# hs-256-expansion-debug.net
KiCad netlist of a schematic drawn in EAGLE
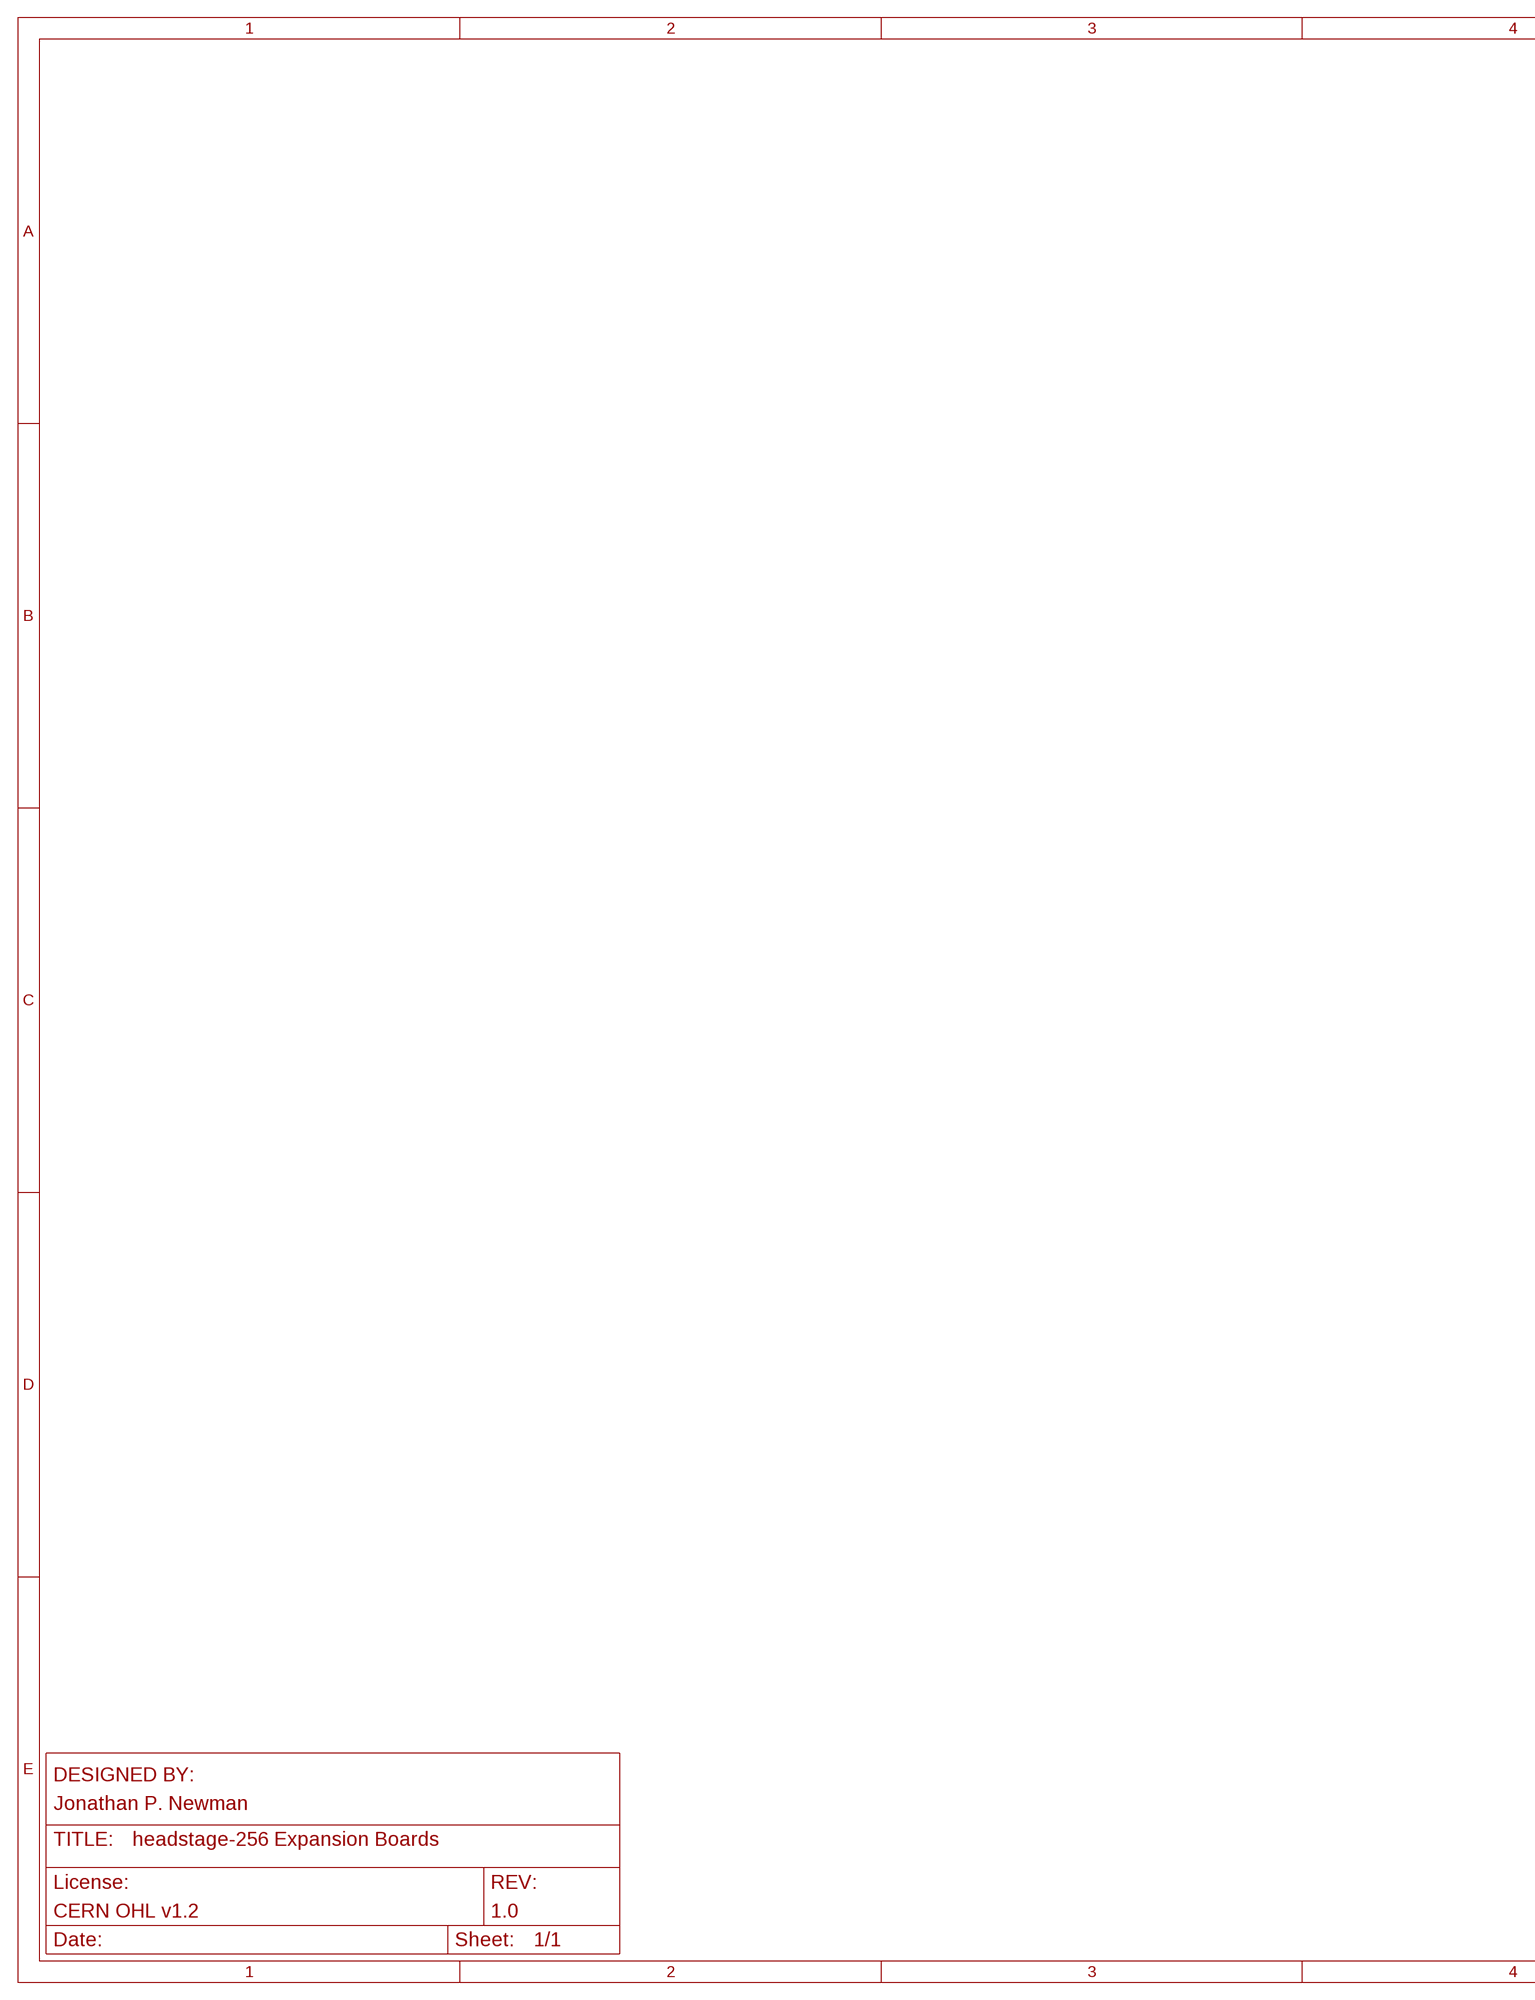
[diagram p0: schematic, sheet 1, part 1 of 2]
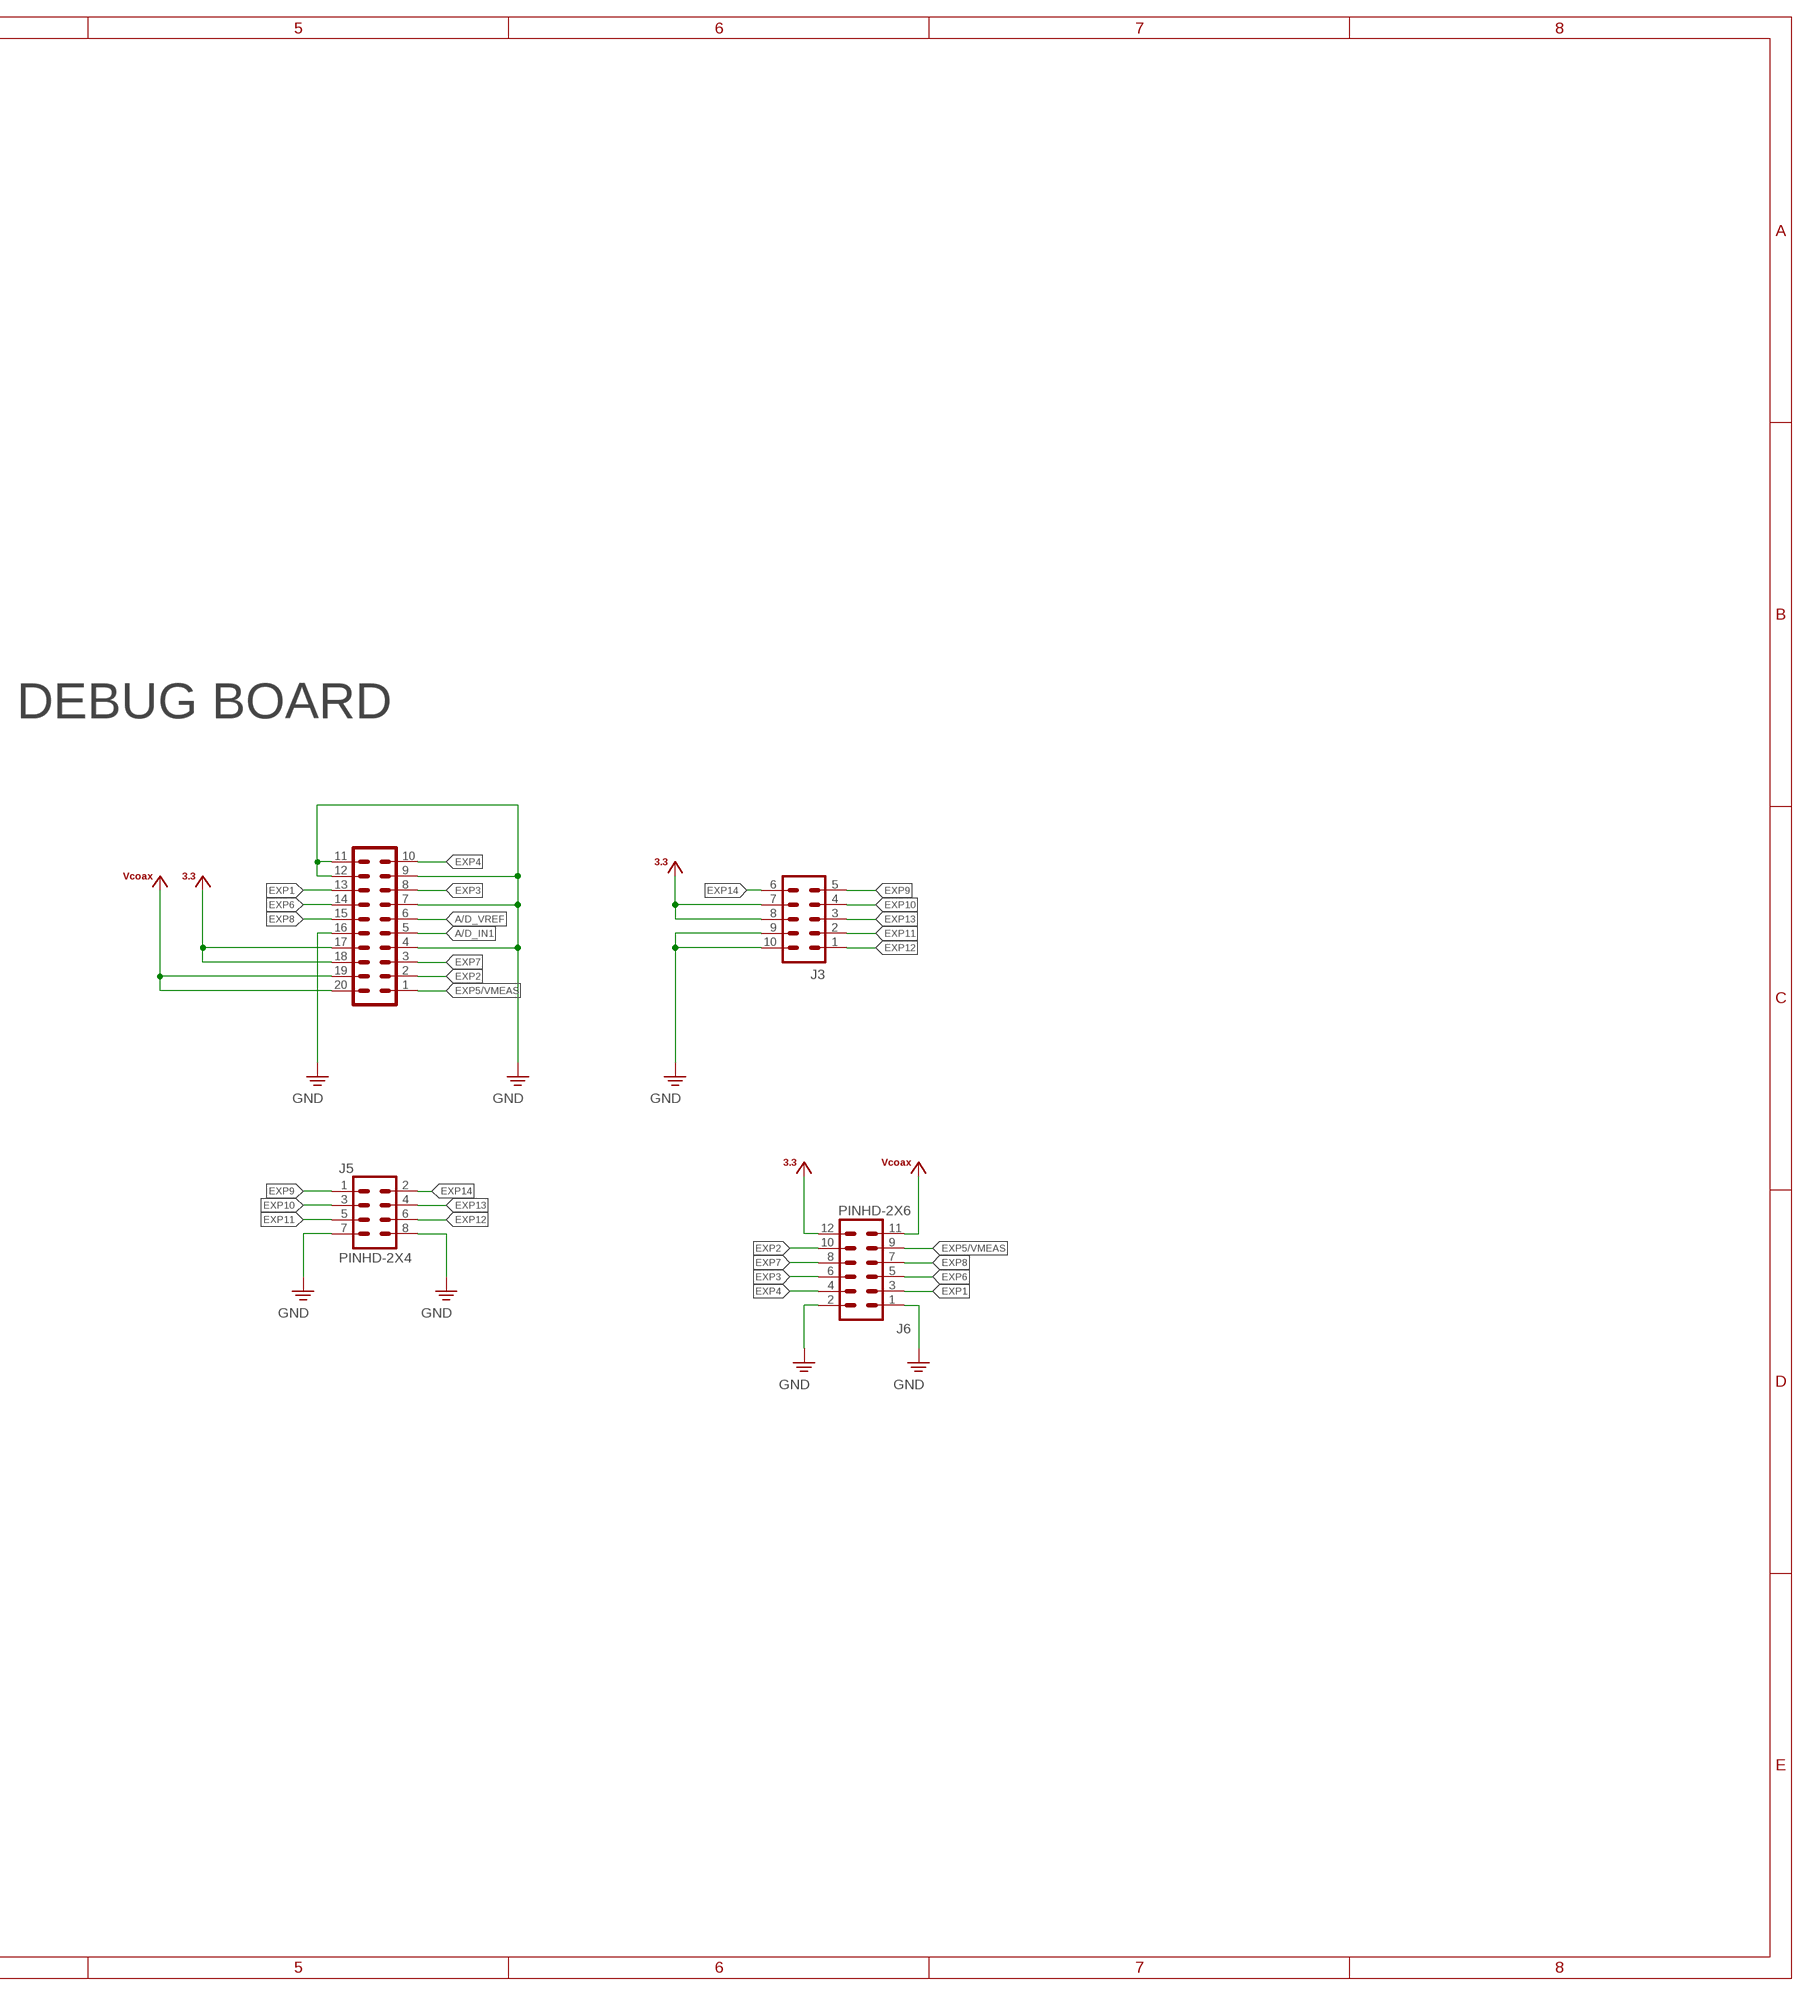
[diagram p1: schematic, sheet 1, part 2 of 2]

(export (version "E")
  (design (tool "Eeschema 10.0.6"))
  (components
    (comp (ref "J3")
      (value "PINHD-2X5_DF40-REC")
      (footprint "eagle-import:DF40-10REC")
      (libsource (lib "eagle-import") (part "PINHD-2X5_DF40-REC"))
    )
    (comp (ref "J4")
      (value "PINHD-2X10_DF40-20REC")
      (footprint "eagle-import:DF40-20REC")
      (libsource (lib "eagle-import") (part "PINHD-2X10_DF40-20REC"))
    )
    (comp (ref "J5")
      (value "PINHD-2X4")
      (footprint "eagle-import:2X04-BIG")
      (libsource (lib "eagle-import") (part "PINHD-2X4"))
    )
    (comp (ref "J6")
      (value "PINHD-2X6")
      (footprint "eagle-import:2X06-BIG")
      (libsource (lib "eagle-import") (part "PINHD-2X6"))
    )
  )
  (nets
    (net (code "1") (name "+3V3") (class "Default")
      (node (ref "J3") (pin "7") (pinfunction "8_7") (pintype "passive"))
      (node (ref "J3") (pin "8") (pinfunction "6_8") (pintype "passive"))
      (node (ref "J4") (pin "17") (pinfunction "17_17") (pintype "bidirectional"))
      (node (ref "J4") (pin "18") (pinfunction "18_18") (pintype "bidirectional"))
      (node (ref "J6") (pin "12") (pinfunction "12_12") (pintype "passive"))
    )
    (net (code "2") (name "+VCOAX") (class "Default")
      (node (ref "J4") (pin "19") (pinfunction "19_19") (pintype "bidirectional"))
      (node (ref "J4") (pin "20") (pinfunction "20_20") (pintype "bidirectional"))
      (node (ref "J6") (pin "11") (pinfunction "11_11") (pintype "passive"))
    )
    (net (code "3") (name "A{slash}D_IN1") (class "Default")
      (node (ref "J4") (pin "5") (pinfunction "5_5") (pintype "bidirectional"))
    )
    (net (code "4") (name "A{slash}D_VREF") (class "Default")
      (node (ref "J4") (pin "6") (pinfunction "6_6") (pintype "bidirectional"))
    )
    (net (code "5") (name "EXP1") (class "Default")
      (node (ref "J4") (pin "13") (pinfunction "13_13") (pintype "bidirectional"))
      (node (ref "J6") (pin "3") (pinfunction "3_3") (pintype "passive"))
    )
    (net (code "6") (name "EXP2") (class "Default")
      (node (ref "J4") (pin "2") (pinfunction "2_2") (pintype "bidirectional"))
      (node (ref "J6") (pin "10") (pinfunction "10_10") (pintype "passive"))
    )
    (net (code "7") (name "EXP3") (class "Default")
      (node (ref "J4") (pin "8") (pinfunction "8_8") (pintype "bidirectional"))
      (node (ref "J6") (pin "6") (pinfunction "6_6") (pintype "passive"))
    )
    (net (code "8") (name "EXP4") (class "Default")
      (node (ref "J4") (pin "10") (pinfunction "10_10") (pintype "bidirectional"))
      (node (ref "J6") (pin "4") (pinfunction "4_4") (pintype "passive"))
    )
    (net (code "9") (name "EXP5{slash}VMEAS") (class "Default")
      (node (ref "J4") (pin "1") (pinfunction "1_1") (pintype "bidirectional"))
      (node (ref "J6") (pin "9") (pinfunction "9_9") (pintype "passive"))
    )
    (net (code "10") (name "EXP6") (class "Default")
      (node (ref "J4") (pin "14") (pinfunction "14_14") (pintype "bidirectional"))
      (node (ref "J6") (pin "5") (pinfunction "5_5") (pintype "passive"))
    )
    (net (code "11") (name "EXP7") (class "Default")
      (node (ref "J4") (pin "3") (pinfunction "3_3") (pintype "bidirectional"))
      (node (ref "J6") (pin "8") (pinfunction "8_8") (pintype "passive"))
    )
    (net (code "12") (name "EXP8") (class "Default")
      (node (ref "J4") (pin "15") (pinfunction "15_15") (pintype "bidirectional"))
      (node (ref "J6") (pin "7") (pinfunction "7_7") (pintype "passive"))
    )
    (net (code "13") (name "EXP9") (class "Default")
      (node (ref "J3") (pin "5") (pinfunction "9_5") (pintype "passive"))
      (node (ref "J5") (pin "1") (pinfunction "1_1") (pintype "passive"))
    )
    (net (code "14") (name "EXP10") (class "Default")
      (node (ref "J3") (pin "4") (pinfunction "7_4") (pintype "passive"))
      (node (ref "J5") (pin "3") (pinfunction "3_3") (pintype "passive"))
    )
    (net (code "15") (name "EXP11") (class "Default")
      (node (ref "J3") (pin "2") (pinfunction "3_2") (pintype "passive"))
      (node (ref "J5") (pin "5") (pinfunction "5_5") (pintype "passive"))
    )
    (net (code "16") (name "EXP12") (class "Default")
      (node (ref "J3") (pin "1") (pinfunction "1_1") (pintype "passive"))
      (node (ref "J5") (pin "6") (pinfunction "6_6") (pintype "passive"))
    )
    (net (code "17") (name "EXP13") (class "Default")
      (node (ref "J3") (pin "3") (pinfunction "5_3") (pintype "passive"))
      (node (ref "J5") (pin "4") (pinfunction "4_4") (pintype "passive"))
    )
    (net (code "18") (name "EXP14") (class "Default")
      (node (ref "J3") (pin "6") (pinfunction "10_6") (pintype "passive"))
      (node (ref "J5") (pin "2") (pinfunction "2_2") (pintype "passive"))
    )
    (net (code "19") (name "GND") (class "Default")
      (node (ref "J3") (pin "10") (pinfunction "2_10") (pintype "passive"))
      (node (ref "J3") (pin "9") (pinfunction "4_9") (pintype "passive"))
      (node (ref "J4") (pin "11") (pinfunction "11_11") (pintype "bidirectional"))
      (node (ref "J4") (pin "12") (pinfunction "12_12") (pintype "bidirectional"))
      (node (ref "J4") (pin "16") (pinfunction "16_16") (pintype "bidirectional"))
      (node (ref "J4") (pin "4") (pinfunction "4_4") (pintype "bidirectional"))
      (node (ref "J4") (pin "7") (pinfunction "7_7") (pintype "bidirectional"))
      (node (ref "J4") (pin "9") (pinfunction "9_9") (pintype "bidirectional"))
      (node (ref "J5") (pin "7") (pinfunction "7_7") (pintype "passive"))
      (node (ref "J5") (pin "8") (pinfunction "8_8") (pintype "passive"))
      (node (ref "J6") (pin "1") (pinfunction "1_1") (pintype "passive"))
      (node (ref "J6") (pin "2") (pinfunction "2_2") (pintype "passive"))
    )
  )
)
